# POWER_1_5V_6A.net
KiCad netlist of a schematic drawn in Altium Designer
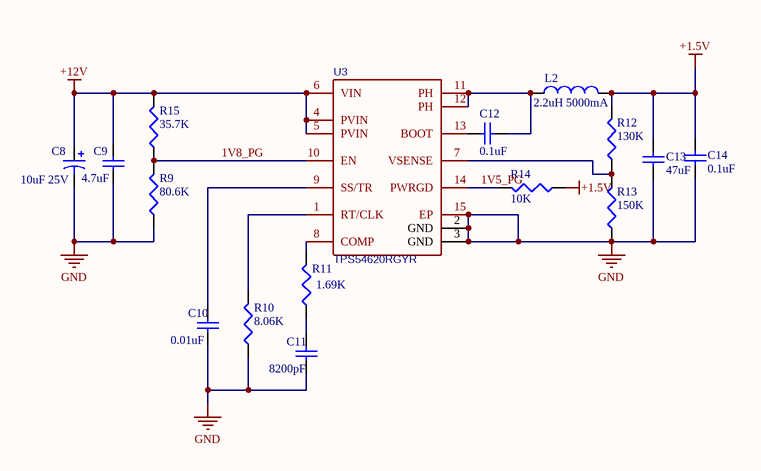
[diagram p0: POWER_1.5V_6A.SchDoc]

(export (version "E")
  (design (tool "Eeschema 10.0.6"))
  (components
    (comp (ref "C8")
      (value "10uF 25V")
      (footprint "47UF_16V")
      (description "Polarized Capacitor (Radial)")
      (fields (field (name "Comment") "Cap Pol1") (field (name "PUBLISHER") "Altium Limited"))
      (libsource (lib "Miscellaneous Devices") (part "Cap Pol1"))
    )
    (comp (ref "C9")
      (value "4.7uF")
      (footprint "C1210")
      (description "Capacitor (Semiconductor SIM Model)")
      (fields (field (name "Comment") "Cap Semi") (field (name "PUBLISHER") "Altium Limited"))
      (libsource (lib "Miscellaneous Devices") (part "Cap Semi"))
    )
    (comp (ref "C10")
      (value "0.01uF")
      (footprint "C1210")
      (description "Capacitor (Semiconductor SIM Model)")
      (fields (field (name "Comment") "Cap Semi") (field (name "PUBLISHER") "Altium Limited"))
      (libsource (lib "Miscellaneous Devices") (part "Cap Semi"))
    )
    (comp (ref "C11")
      (value "8200pF")
      (footprint "C1210")
      (description "Capacitor (Semiconductor SIM Model)")
      (fields (field (name "Comment") "Cap Semi") (field (name "PUBLISHER") "Altium Limited"))
      (libsource (lib "Miscellaneous Devices") (part "Cap Semi"))
    )
    (comp (ref "C12")
      (value "0.1uF")
      (footprint "C1210")
      (description "Capacitor (Semiconductor SIM Model)")
      (fields (field (name "Comment") "Cap Semi") (field (name "PUBLISHER") "Altium Limited"))
      (libsource (lib "Miscellaneous Devices") (part "Cap Semi"))
    )
    (comp (ref "C13")
      (value "47uF")
      (footprint "C1210")
      (description "Capacitor (Semiconductor SIM Model)")
      (fields (field (name "Comment") "Cap Semi") (field (name "PUBLISHER") "Altium Limited"))
      (libsource (lib "Miscellaneous Devices") (part "Cap Semi"))
    )
    (comp (ref "C14")
      (value "0.1uF")
      (footprint "C1210")
      (description "Capacitor (Semiconductor SIM Model)")
      (fields (field (name "Comment") "Cap Semi") (field (name "PUBLISHER") "Altium Limited"))
      (libsource (lib "Miscellaneous Devices") (part "Cap Semi"))
    )
    (comp (ref "L2")
      (value "2.2uH 5000mA")
      (footprint "IND-SMD_L5.5-W5.2")
      (description "Inductor")
      (fields (field (name "PUBLISHER") "Altium Limited"))
      (libsource (lib "Miscellaneous Devices") (part "Inductor"))
    )
    (comp (ref "R9")
      (value "80.6K")
      (footprint "J1-0603")
      (description "Resistor")
      (fields (field (name "Comment") "Res3") (field (name "PUBLISHER") "Altium Limited"))
      (libsource (lib "Miscellaneous Devices") (part "Res3"))
    )
    (comp (ref "R10")
      (value "8.06K")
      (footprint "J1-0603")
      (description "Resistor")
      (fields (field (name "Comment") "Res3") (field (name "PUBLISHER") "Altium Limited"))
      (libsource (lib "Miscellaneous Devices") (part "Res3"))
    )
    (comp (ref "R11")
      (value "1.69K")
      (footprint "J1-0603")
      (description "Resistor")
      (fields (field (name "Comment") "Res3") (field (name "PUBLISHER") "Altium Limited"))
      (libsource (lib "Miscellaneous Devices") (part "Res3"))
    )
    (comp (ref "R12")
      (value "130K")
      (footprint "J1-0603")
      (description "Resistor")
      (fields (field (name "Comment") "Res3") (field (name "PUBLISHER") "Altium Limited"))
      (libsource (lib "Miscellaneous Devices") (part "Res3"))
    )
    (comp (ref "R13")
      (value "150K")
      (footprint "J1-0603")
      (description "Resistor")
      (fields (field (name "Comment") "Res3") (field (name "PUBLISHER") "Altium Limited"))
      (libsource (lib "Miscellaneous Devices") (part "Res3"))
    )
    (comp (ref "R14")
      (value "10K")
      (footprint "J1-0603")
      (description "Resistor")
      (fields (field (name "Comment") "Res3") (field (name "PUBLISHER") "Altium Limited"))
      (libsource (lib "Miscellaneous Devices") (part "Res3"))
    )
    (comp (ref "R15")
      (value "35.7K")
      (footprint "J1-0603")
      (description "Resistor")
      (fields (field (name "Comment") "Res3") (field (name "PUBLISHER") "Altium Limited"))
      (libsource (lib "Miscellaneous Devices") (part "Res3"))
    )
    (comp (ref "U3")
      (value "TPS54620RGYR")
      (footprint "VQFN-14_L3.5-W3.5-P0.50-TL-EP_TPS54622RHLT")
      (fields (field (name "BOM_SUPPLIER PART") "C29438"))
      (libsource (lib "power_chip") (part "TPS54620RGYR"))
    )
  )
  (nets
    (net (code "1") (name "+1.5V") (class "Default")
      (node (ref "C13") (pin "1") (pinfunction "1_1") (pintype "passive"))
      (node (ref "C14") (pin "1") (pinfunction "1_1") (pintype "passive"))
      (node (ref "L2") (pin "2") (pinfunction "2_2") (pintype "passive"))
      (node (ref "R12") (pin "2") (pinfunction "2_2") (pintype "passive"))
      (node (ref "R14") (pin "1") (pinfunction "1_1") (pintype "passive"))
    )
    (net (code "2") (name "+12V") (class "Default")
      (node (ref "C8") (pin "1") (pinfunction "1_1") (pintype "passive"))
      (node (ref "C9") (pin "2") (pinfunction "2_2") (pintype "passive"))
      (node (ref "R15") (pin "2") (pinfunction "2_2") (pintype "passive"))
      (node (ref "U3") (pin "4") (pinfunction "PVIN_4") (pintype "passive"))
      (node (ref "U3") (pin "5") (pinfunction "PVIN_5") (pintype "passive"))
      (node (ref "U3") (pin "6") (pinfunction "VIN_6") (pintype "passive"))
    )
    (net (code "3") (name "/1V5_PG") (class "Default")
      (node (ref "R14") (pin "2") (pinfunction "2_2") (pintype "passive"))
      (node (ref "U3") (pin "14") (pinfunction "PWRGD_14") (pintype "passive"))
    )
    (net (code "4") (name "/1V8_PG") (class "Default")
      (node (ref "R15") (pin "1") (pinfunction "1_1") (pintype "passive"))
      (node (ref "R9") (pin "2") (pinfunction "2_2") (pintype "passive"))
      (node (ref "U3") (pin "10") (pinfunction "EN_10") (pintype "passive"))
    )
    (net (code "5") (name "GND") (class "Default")
      (node (ref "C10") (pin "1") (pinfunction "1_1") (pintype "passive"))
      (node (ref "C11") (pin "1") (pinfunction "1_1") (pintype "passive"))
      (node (ref "C13") (pin "2") (pinfunction "2_2") (pintype "passive"))
      (node (ref "C14") (pin "2") (pinfunction "2_2") (pintype "passive"))
      (node (ref "C8") (pin "2") (pinfunction "2_2") (pintype "passive"))
      (node (ref "C9") (pin "1") (pinfunction "1_1") (pintype "passive"))
      (node (ref "R10") (pin "1") (pinfunction "1_1") (pintype "passive"))
      (node (ref "R13") (pin "1") (pinfunction "1_1") (pintype "passive"))
      (node (ref "R9") (pin "1") (pinfunction "1_1") (pintype "passive"))
      (node (ref "U3") (pin "15") (pinfunction "EP_15") (pintype "passive"))
      (node (ref "U3") (pin "2") (pinfunction "GND_2") (pintype "passive"))
      (node (ref "U3") (pin "3") (pinfunction "GND_3") (pintype "passive"))
    )
    (net (code "6") (name "Net-(C11-Pad2)") (class "Default")
      (node (ref "C11") (pin "2") (pinfunction "2_2") (pintype "passive"))
      (node (ref "R11") (pin "1") (pinfunction "1_1") (pintype "passive"))
    )
    (net (code "7") (name "Net-(C12-Pad1)") (class "Default")
      (node (ref "C12") (pin "1") (pinfunction "1_1") (pintype "passive"))
      (node (ref "L2") (pin "1") (pinfunction "1_1") (pintype "passive"))
      (node (ref "U3") (pin "11") (pinfunction "PH_11") (pintype "passive"))
      (node (ref "U3") (pin "12") (pinfunction "PH_12") (pintype "passive"))
    )
    (net (code "8") (name "Net-(U3-BOOT)") (class "Default")
      (node (ref "C12") (pin "2") (pinfunction "2_2") (pintype "passive"))
      (node (ref "U3") (pin "13") (pinfunction "BOOT_13") (pintype "passive"))
    )
    (net (code "9") (name "Net-(U3-COMP)") (class "Default")
      (node (ref "R11") (pin "2") (pinfunction "2_2") (pintype "passive"))
      (node (ref "U3") (pin "8") (pinfunction "COMP_8") (pintype "passive"))
    )
    (net (code "10") (name "Net-(U3-RT{slash}CLK)") (class "Default")
      (node (ref "R10") (pin "2") (pinfunction "2_2") (pintype "passive"))
      (node (ref "U3") (pin "1") (pinfunction "RT/CLK_1") (pintype "passive"))
    )
    (net (code "11") (name "Net-(U3-SS{slash}TR)") (class "Default")
      (node (ref "C10") (pin "2") (pinfunction "2_2") (pintype "passive"))
      (node (ref "U3") (pin "9") (pinfunction "SS/TR_9") (pintype "passive"))
    )
    (net (code "12") (name "Net-(U3-VSENSE)") (class "Default")
      (node (ref "R12") (pin "1") (pinfunction "1_1") (pintype "passive"))
      (node (ref "R13") (pin "2") (pinfunction "2_2") (pintype "passive"))
      (node (ref "U3") (pin "7") (pinfunction "VSENSE_7") (pintype "passive"))
    )
  )
)
